# Water_Intrustion.net
KiCad netlist of a schematic drawn in Altium Designer
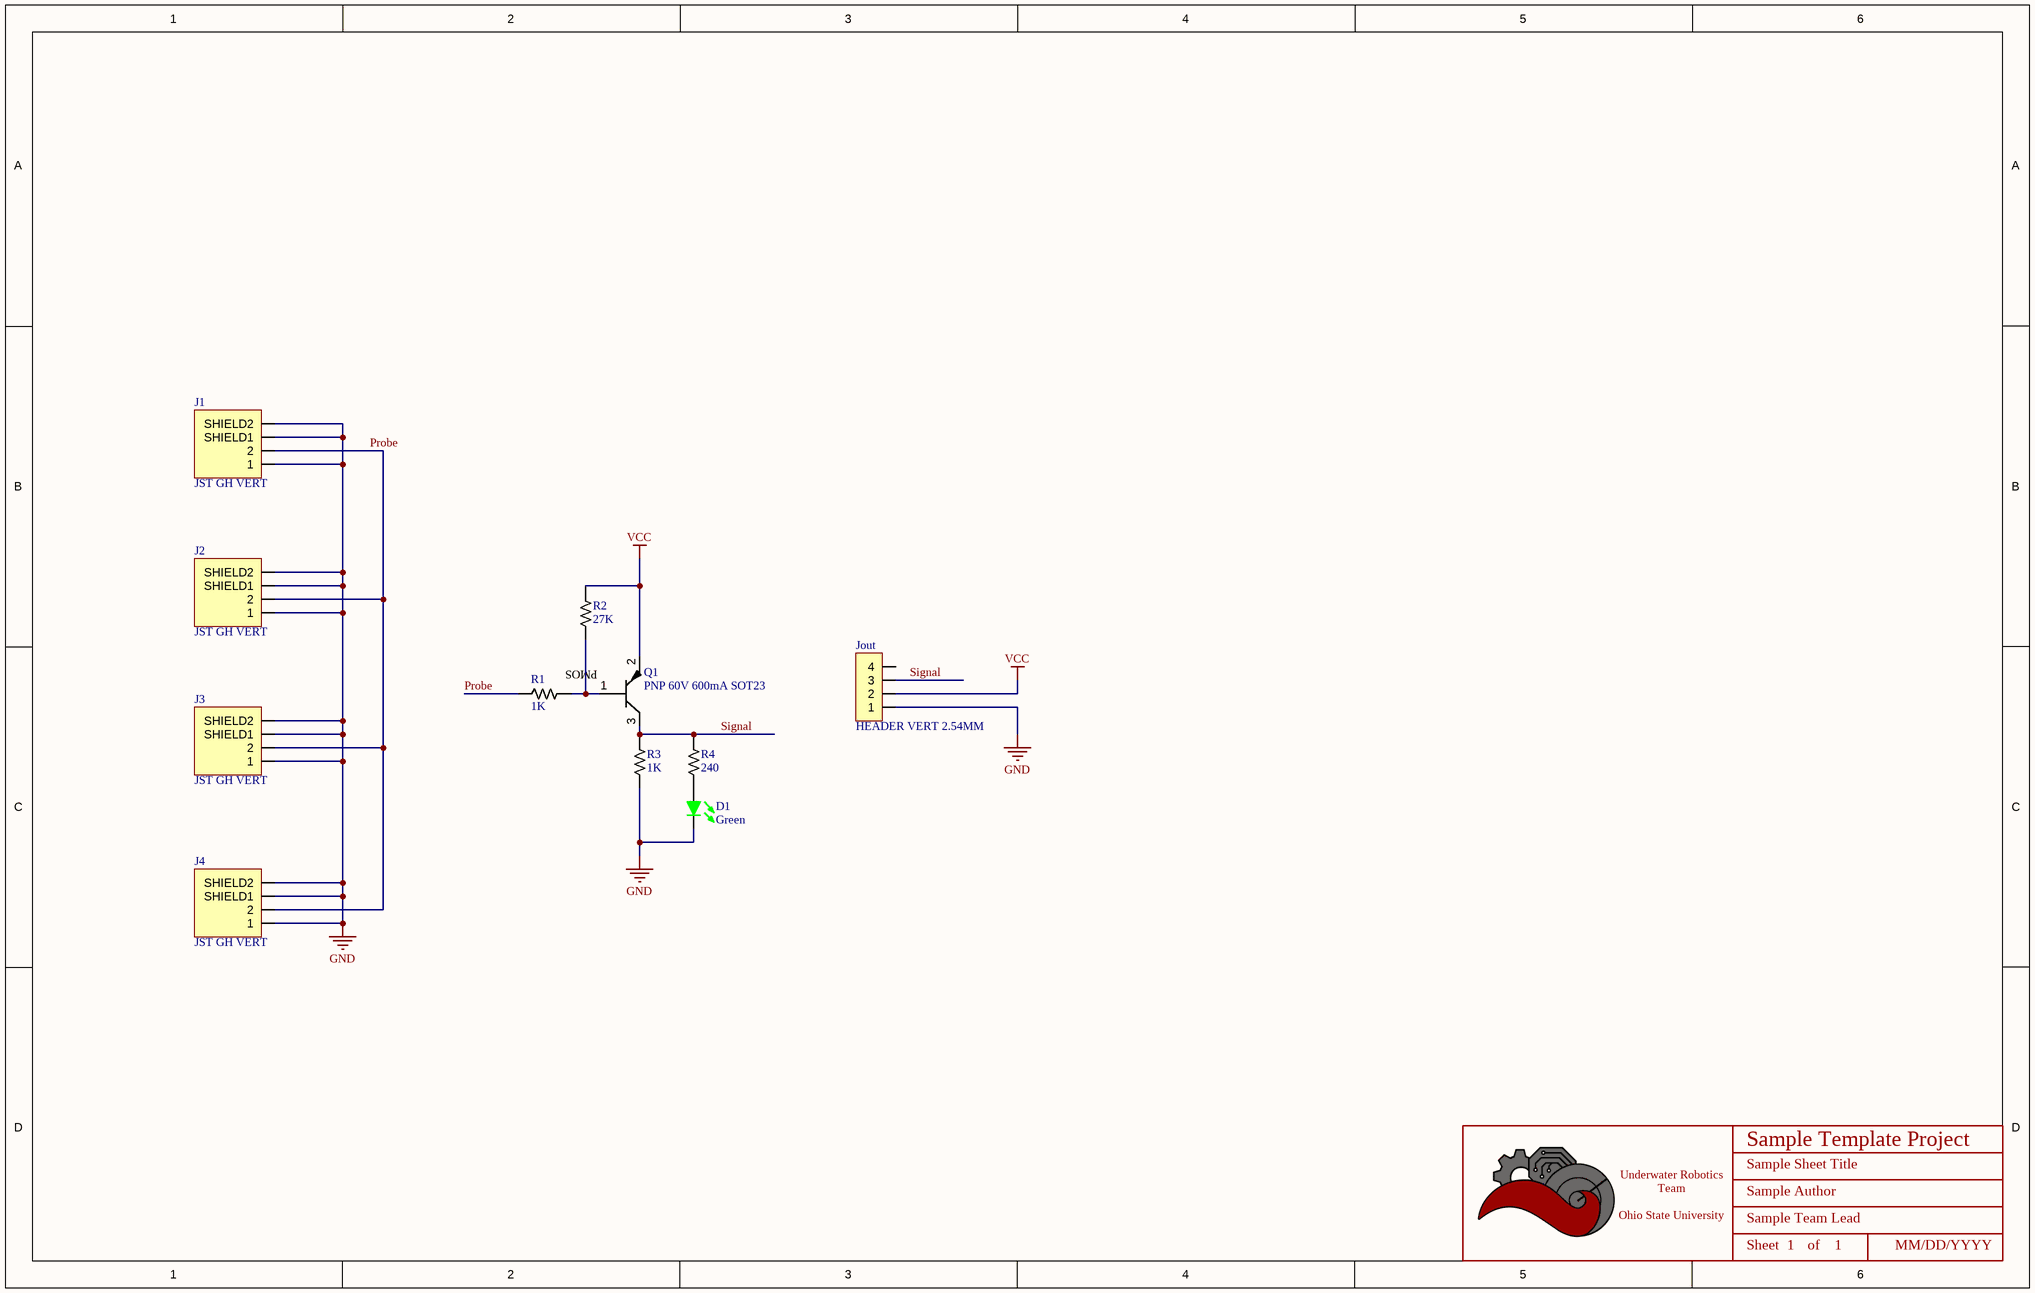
[diagram p0: Water Intrustion.SchDoc]

(export (version "E")
  (design (tool "Eeschema 10.0.6"))
  (components
    (comp (ref "*")
      (value "Title_Block")
      (footprint "LOGO")
      (description "UWRT Schematic Title Block Template\r\n\r\nCreated June 2021, Dylan Trainor")
      (libsource (lib "UWRT") (part "Title_Block"))
    )
    (comp (ref "D1")
      (value "IN-S63AT5G")
      (footprint "LED_0603")
      (description "LED Green Vf= 3V If = 0.005A\r\nIN-S63AT5G")
      (fields (field (name "COLOR") "Green") (field (name "MADE BY") "Robert Pafford"))
      (libsource (lib "Diodes") (part "LED_Green_0603_3V"))
    )
    (comp (ref "J1")
      (value "JST GH VERT")
      (footprint "CONN_JST_SM02B-GHS-TB(LF)(SN)")
      (description "JST GH Pitch 2 Pos Vertical")
      (fields (field (name "MANUFACTURER") "JST") (field (name "CREATED BY") "Robert P"))
      (libsource (lib "Connectors") (part "CONN_JST_GH_2POS_VERT"))
    )
    (comp (ref "J2")
      (value "JST GH VERT")
      (footprint "CONN_JST_SM02B-GHS-TB(LF)(SN)")
      (description "JST GH Pitch 2 Pos Vertical")
      (fields (field (name "MANUFACTURER") "JST") (field (name "CREATED BY") "Robert P"))
      (libsource (lib "Connectors") (part "CONN_JST_GH_2POS_VERT"))
    )
    (comp (ref "J3")
      (value "JST GH VERT")
      (footprint "CONN_JST_SM02B-GHS-TB(LF)(SN)")
      (description "JST GH Pitch 2 Pos Vertical")
      (fields (field (name "MANUFACTURER") "JST") (field (name "CREATED BY") "Robert P"))
      (libsource (lib "Connectors") (part "CONN_JST_GH_2POS_VERT"))
    )
    (comp (ref "J4")
      (value "JST GH VERT")
      (footprint "CONN_JST_SM02B-GHS-TB(LF)(SN)")
      (description "JST GH Pitch 2 Pos Vertical")
      (fields (field (name "MANUFACTURER") "JST") (field (name "CREATED BY") "Robert P"))
      (libsource (lib "Connectors") (part "CONN_JST_GH_2POS_VERT"))
    )
    (comp (ref "Jout")
      (value "HEADER VERT 2.54MM")
      (footprint "HEADER_4PIN_2.54MM")
      (description "CONN HEADER VERT 4POS 2.54MM")
      (fields (field (name "MADE BY") "Robert Pafford"))
      (libsource (lib "Connectors") (part "HEADER_4PIN_2.54MM"))
    )
    (comp (ref "Q1")
      (value "PNP 60V 600mA SOT23")
      (footprint "SOT-23-3")
      (description "PNP 60 V 600mA Surface Mount SOT-23")
      (fields
        (field (name "MANUFACTURER_PART_NUMBER") "MMBT2907A-7-F")
        (field (name "CREATED BY") "Robert Pafford")
      )
      (libsource (lib "Transistors") (part "MMBT2907A-7-F"))
    )
    (comp (ref "R1")
      (value "1k Ohm 5% 1/8W")
      (footprint "RESISTOR_0603")
      (description "RES 1k OHM 5% 1/8W 0603")
      (fields
        (field (name "TOLERANCE") "+/- 5%")
        (field (name "VALUE  (OHMS)") "1K")
        (field (name "MADE BY") "Robert Pafford")
      )
      (libsource (lib "Resistors") (part "RESISTOR_1K_0603"))
    )
    (comp (ref "R2")
      (value "27k Ohm 5% 1/8W")
      (footprint "RESISTOR_0603")
      (description "RES SMD 27K OHM 5% 1/10W 0603")
      (fields
        (field (name "TOLERANCE") "+/- 5%")
        (field (name "VALUE  (OHMS)") "27K")
        (field (name "MADE BY") "John Ulm")
      )
      (libsource (lib "Resistors") (part "RESISTOR_27K_0603_1"))
    )
    (comp (ref "R3")
      (value "1k Ohm 5% 1/8W")
      (footprint "RESISTOR_0603")
      (description "RES 1k OHM 5% 1/8W 0603")
      (fields
        (field (name "TOLERANCE") "+/- 5%")
        (field (name "VALUE  (OHMS)") "1K")
        (field (name "MADE BY") "Robert Pafford")
      )
      (libsource (lib "Resistors") (part "RESISTOR_1K_0603"))
    )
    (comp (ref "R4")
      (value "RES SMD 240 OHM 5% 1/10W 0603")
      (footprint "RESISTOR_0603")
      (fields
        (field (name "TOLERANCE") "+/- 5%")
        (field (name "VALUE  (OHMS)") "240")
        (field (name "MADE BY") "John Ulm")
      )
      (libsource (lib "Resistors") (part "RESISTOR_240_0603"))
    )
  )
  (nets
    (net (code "1") (name "/Probe") (class "Default")
      (node (ref "J1") (pin "2") (pinfunction "2_2") (pintype "passive"))
      (node (ref "J2") (pin "2") (pinfunction "2_2") (pintype "passive"))
      (node (ref "J3") (pin "2") (pinfunction "2_2") (pintype "passive"))
      (node (ref "J4") (pin "2") (pinfunction "2_2") (pintype "passive"))
      (node (ref "R1") (pin "2") (pinfunction "2_2") (pintype "passive"))
    )
    (net (code "2") (name "/Signal") (class "Default")
      (node (ref "Jout") (pin "3") (pinfunction "3_3") (pintype "passive"))
      (node (ref "Q1") (pin "3") (pinfunction "3_3") (pintype "passive"))
      (node (ref "R3") (pin "1") (pinfunction "1_1") (pintype "passive"))
      (node (ref "R4") (pin "1") (pinfunction "1_1") (pintype "passive"))
    )
    (net (code "3") (name "GND") (class "Default")
      (node (ref "D1") (pin "2") (pinfunction "2_2") (pintype "passive"))
      (node (ref "J1") (pin "1") (pinfunction "1_1") (pintype "passive"))
      (node (ref "J1") (pin "S1") (pinfunction "SHIELD1_S1") (pintype "passive"))
      (node (ref "J1") (pin "S2") (pinfunction "SHIELD2_S2") (pintype "passive"))
      (node (ref "J2") (pin "1") (pinfunction "1_1") (pintype "passive"))
      (node (ref "J2") (pin "S1") (pinfunction "SHIELD1_S1") (pintype "passive"))
      (node (ref "J2") (pin "S2") (pinfunction "SHIELD2_S2") (pintype "passive"))
      (node (ref "J3") (pin "1") (pinfunction "1_1") (pintype "passive"))
      (node (ref "J3") (pin "S1") (pinfunction "SHIELD1_S1") (pintype "passive"))
      (node (ref "J3") (pin "S2") (pinfunction "SHIELD2_S2") (pintype "passive"))
      (node (ref "J4") (pin "1") (pinfunction "1_1") (pintype "passive"))
      (node (ref "J4") (pin "S1") (pinfunction "SHIELD1_S1") (pintype "passive"))
      (node (ref "J4") (pin "S2") (pinfunction "SHIELD2_S2") (pintype "passive"))
      (node (ref "Jout") (pin "1") (pinfunction "1_1") (pintype "passive"))
      (node (ref "R3") (pin "2") (pinfunction "2_2") (pintype "passive"))
    )
    (net (code "4") (name "Net-(D1-Pad1)") (class "Default")
      (node (ref "D1") (pin "1") (pinfunction "1_1") (pintype "passive"))
      (node (ref "R4") (pin "2") (pinfunction "2_2") (pintype "passive"))
    )
    (net (code "5") (name "Net-(Q1-Pad1)") (class "Default")
      (node (ref "Q1") (pin "1") (pinfunction "1_1") (pintype "passive"))
      (node (ref "R1") (pin "1") (pinfunction "1_1") (pintype "passive"))
      (node (ref "R2") (pin "2") (pinfunction "2_2") (pintype "passive"))
    )
    (net (code "6") (name "VCC") (class "Default")
      (node (ref "Jout") (pin "2") (pinfunction "2_2") (pintype "passive"))
      (node (ref "Q1") (pin "2") (pinfunction "2_2") (pintype "passive"))
      (node (ref "R2") (pin "1") (pinfunction "1_1") (pintype "passive"))
    )
    (net (code "7") (name "unconnected-(Jout-Pad4)") (class "Default")
      (node (ref "Jout") (pin "4") (pinfunction "4_4") (pintype "passive"))
    )
  )
)
